# ZOE-M8Q_GPS.net
KiCad netlist of a schematic drawn in EAGLE
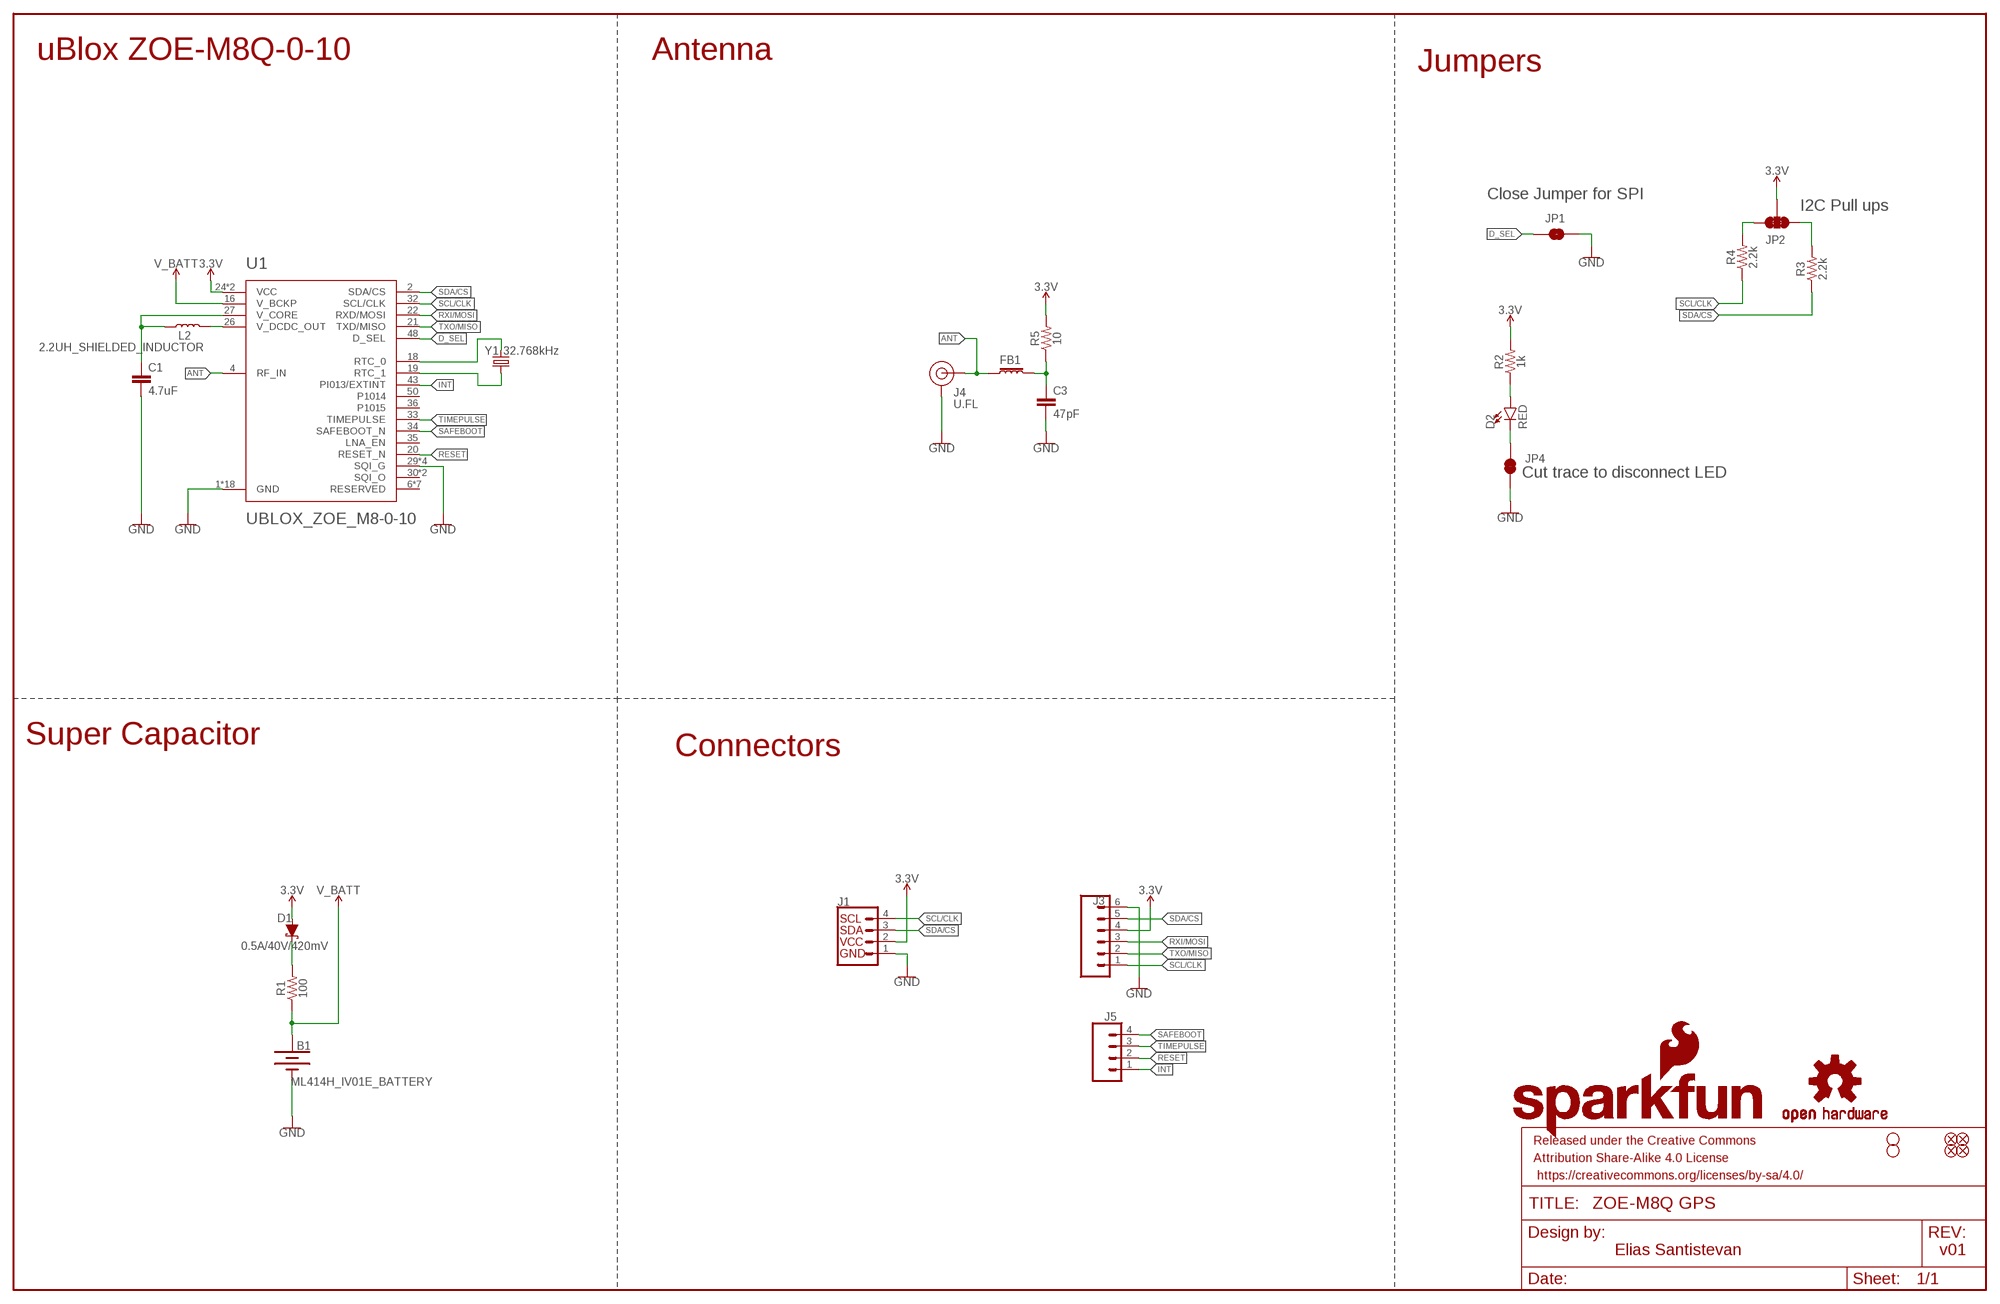
[diagram p0: schematic, sheet 1]

(export (version "E")
  (design (tool "Eeschema 10.0.6"))
  (components
    (comp (ref "B1")
      (value "ML414H_IV01E_BATTERY")
      (footprint "eagle-import:ML414H_IV01E")
      (libsource (lib "eagle-import") (part "ML414H_IV01E_BATTERY"))
    )
    (comp (ref "C1")
      (value "4.7uF")
      (footprint "eagle-import:0603")
      (libsource (lib "eagle-import") (part "4.7UF-0603-6.3V-(10%)"))
    )
    (comp (ref "C3")
      (value "47pF")
      (footprint "eagle-import:0603")
      (libsource (lib "eagle-import") (part "47PF-0603-50V-5%"))
    )
    (comp (ref "D1")
      (value "0.5A/40V/420mV")
      (footprint "eagle-import:SOD-323")
      (libsource (lib "eagle-import") (part "DIODE-SCHOTTKY-PMEG4005EJ"))
    )
    (comp (ref "D2")
      (value "RED")
      (footprint "eagle-import:LED-0603")
      (libsource (lib "eagle-import") (part "LED-RED0603"))
    )
    (comp (ref "FB1")
      (value "FERRITE_BEAD-120_OHM-0402")
      (footprint "eagle-import:0402")
      (fields (field (name "MFG_PART") "BLM15HB121SN1D"))
      (libsource (lib "eagle-import") (part "FERRITE_BEAD-120_OHM-0402"))
    )
    (comp (ref "FD1")
      (value "FIDUCIALUFIDUCIAL")
      (footprint "eagle-import:FIDUCIAL-MICRO")
      (libsource (lib "eagle-import") (part "FIDUCIALUFIDUCIAL"))
    )
    (comp (ref "FD2")
      (value "FIDUCIALUFIDUCIAL")
      (footprint "eagle-import:FIDUCIAL-MICRO")
      (libsource (lib "eagle-import") (part "FIDUCIALUFIDUCIAL"))
    )
    (comp (ref "FD3")
      (value "FIDUCIALUFIDUCIAL")
      (footprint "eagle-import:FIDUCIAL-MICRO")
      (libsource (lib "eagle-import") (part "FIDUCIALUFIDUCIAL"))
    )
    (comp (ref "FD4")
      (value "FIDUCIALUFIDUCIAL")
      (footprint "eagle-import:FIDUCIAL-MICRO")
      (libsource (lib "eagle-import") (part "FIDUCIALUFIDUCIAL"))
    )
    (comp (ref "FRAME1")
      (value "FRAME-LEDGER")
      (footprint "eagle-import:CREATIVE_COMMONS")
      (libsource (lib "eagle-import") (part "FRAME-LEDGER"))
    )
    (comp (ref "H2")
      (value "STAND-OFFTIGHT")
      (footprint "eagle-import:STAND-OFF-TIGHT")
      (libsource (lib "eagle-import") (part "STAND-OFFTIGHT"))
    )
    (comp (ref "H3")
      (value "STAND-OFFTIGHT")
      (footprint "eagle-import:STAND-OFF-TIGHT")
      (libsource (lib "eagle-import") (part "STAND-OFFTIGHT"))
    )
    (comp (ref "J1")
      (value "QWIIC_CONNECTORJS-1MM")
      (footprint "eagle-import:JST04_1MM_RA")
      (libsource (lib "eagle-import") (part "QWIIC_CONNECTORJS-1MM"))
    )
    (comp (ref "J3")
      (value "CONN_06NO_SILK_NO_POP")
      (footprint "eagle-import:1X06_NO_SILK")
      (libsource (lib "eagle-import") (part "CONN_06NO_SILK_NO_POP"))
    )
    (comp (ref "J4")
      (value "U.FL")
      (footprint "eagle-import:U.FL")
      (libsource (lib "eagle-import") (part "U.FL2PIN"))
    )
    (comp (ref "J5")
      (value "CONN_041X04_NO_SILK")
      (footprint "eagle-import:1X04_NO_SILK")
      (libsource (lib "eagle-import") (part "CONN_041X04_NO_SILK"))
    )
    (comp (ref "JP1")
      (value "JUMPER-SMT_2_NO_SILK")
      (footprint "eagle-import:SMT-JUMPER_2_NO_SILK")
      (libsource (lib "eagle-import") (part "JUMPER-SMT_2_NO_SILK"))
    )
    (comp (ref "JP2")
      (value "JUMPER-SMT_3_2-NC_TRACE_SILK")
      (footprint "eagle-import:SMT-JUMPER_3_2-NC_TRACE_SILK")
      (libsource (lib "eagle-import") (part "JUMPER-SMT_3_2-NC_TRACE_SILK"))
    )
    (comp (ref "JP4")
      (value "JUMPER-SMT_2_NC_TRACE_SILK")
      (footprint "eagle-import:SMT-JUMPER_2_NC_TRACE_SILK")
      (libsource (lib "eagle-import") (part "JUMPER-SMT_2_NC_TRACE_SILK"))
    )
    (comp (ref "L2")
      (value "2.2UH_SHIELDED_INDUCTOR")
      (footprint "eagle-import:UNIQUE_0806_NDUC")
      (libsource (lib "eagle-import") (part "2.2UH_SHIELDED_INDUCTOR"))
    )
    (comp (ref "LOGO1")
      (value "SFE_LOGO_NAME_FLAME.1_INCH")
      (footprint "eagle-import:SFE_LOGO_NAME_FLAME_.1")
      (libsource (lib "eagle-import") (part "SFE_LOGO_NAME_FLAME.1_INCH"))
    )
    (comp (ref "LOGO2")
      (value "OSHW-LOGOS")
      (footprint "eagle-import:OSHW-LOGO-S")
      (libsource (lib "eagle-import") (part "OSHW-LOGOS"))
    )
    (comp (ref "LOGO3")
      (value "SFE_LOGO_FLAME.1_INCH")
      (footprint "eagle-import:SFE_LOGO_FLAME_.1")
      (libsource (lib "eagle-import") (part "SFE_LOGO_FLAME.1_INCH"))
    )
    (comp (ref "R1")
      (value "100")
      (footprint "eagle-import:0603")
      (libsource (lib "eagle-import") (part "100OHM-0603-1/10W-1%"))
    )
    (comp (ref "R2")
      (value "1k")
      (footprint "eagle-import:0603")
      (libsource (lib "eagle-import") (part "1KOHM-0603-1/10W-1%"))
    )
    (comp (ref "R3")
      (value "2.2k")
      (footprint "eagle-import:0603")
      (libsource (lib "eagle-import") (part "2.2KOHM-0603-1/10W-1%"))
    )
    (comp (ref "R4")
      (value "2.2k")
      (footprint "eagle-import:0603")
      (libsource (lib "eagle-import") (part "2.2KOHM-0603-1/10W-1%"))
    )
    (comp (ref "R5")
      (value "10")
      (footprint "eagle-import:0603")
      (libsource (lib "eagle-import") (part "10OHM-0603-1/10W-1%"))
    )
    (comp (ref "U1")
      (value "UBLOX_ZOE_M8-0-10")
      (footprint "eagle-import:UBLOX_ZOE_M8-0-10")
      (libsource (lib "eagle-import") (part "UBLOX_ZOE_M8-0-10"))
    )
    (comp (ref "Y1")
      (value "32.768kHz")
      (footprint "eagle-import:CRYSTAL-SMD-3.2X1.5MM")
      (libsource (lib "eagle-import") (part "CRYSTAL-32.768KHZSMD-3.2X1.5"))
    )
  )
  (nets
    (net (code "1") (name "3.3V") (class "Default")
      (node (ref "D1") (pin "A") (pinfunction "A_A") (pintype "passive"))
      (node (ref "J1") (pin "2") (pinfunction "2_2") (pintype "power_in"))
      (node (ref "J3") (pin "4") (pinfunction "4_4") (pintype "passive"))
      (node (ref "JP2") (pin "2") (pinfunction "2_2") (pintype "passive"))
      (node (ref "R2") (pin "2") (pinfunction "2_2") (pintype "passive"))
      (node (ref "R5") (pin "2") (pinfunction "2_2") (pintype "passive"))
      (node (ref "U1") (pin "24") (pinfunction "VCC_24") (pintype "power_in"))
      (node (ref "U1") (pin "25") (pinfunction "VCC_25") (pintype "power_in"))
    )
    (net (code "2") (name "ANT") (class "Default")
      (node (ref "FB1") (pin "1") (pinfunction "1_1") (pintype "passive"))
      (node (ref "J4") (pin "FEED") (pinfunction "SIGNAL_FEED") (pintype "bidirectional"))
      (node (ref "U1") (pin "4") (pinfunction "RF_IN_4") (pintype "bidirectional"))
    )
    (net (code "3") (name "D_SEL") (class "Default")
      (node (ref "JP1") (pin "1") (pinfunction "1_1") (pintype "passive"))
      (node (ref "U1") (pin "48") (pinfunction "D_SEL_48") (pintype "bidirectional"))
    )
    (net (code "4") (name "GND") (class "Default")
      (node (ref "B1") (pin "-") (pinfunction "-_-") (pintype "power_in"))
      (node (ref "C1") (pin "2") (pinfunction "2_2") (pintype "passive"))
      (node (ref "C3") (pin "2") (pinfunction "2_2") (pintype "passive"))
      (node (ref "J1") (pin "1") (pinfunction "1_1") (pintype "power_in"))
      (node (ref "J3") (pin "6") (pinfunction "6_6") (pintype "passive"))
      (node (ref "J4") (pin "1") (pinfunction "GND_1") (pintype "bidirectional"))
      (node (ref "J4") (pin "2") (pinfunction "GND_2") (pintype "bidirectional"))
      (node (ref "JP1") (pin "2") (pinfunction "2_2") (pintype "passive"))
      (node (ref "JP4") (pin "1") (pinfunction "1_1") (pintype "passive"))
      (node (ref "U1") (pin "1") (pinfunction "GND_1") (pintype "power_in"))
      (node (ref "U1") (pin "10") (pinfunction "GND_10") (pintype "power_in"))
      (node (ref "U1") (pin "11") (pinfunction "GND_11") (pintype "power_in"))
      (node (ref "U1") (pin "12") (pinfunction "GND_12") (pintype "power_in"))
      (node (ref "U1") (pin "17") (pinfunction "GND_17") (pintype "power_in"))
      (node (ref "U1") (pin "23") (pinfunction "GND_23") (pintype "power_in"))
      (node (ref "U1") (pin "29") (pinfunction "SQI_G_29") (pintype "bidirectional"))
      (node (ref "U1") (pin "3") (pinfunction "GND_3") (pintype "power_in"))
      (node (ref "U1") (pin "31") (pinfunction "SQI_G_31") (pintype "bidirectional"))
      (node (ref "U1") (pin "37") (pinfunction "GND_37") (pintype "power_in"))
      (node (ref "U1") (pin "38") (pinfunction "GND_38") (pintype "power_in"))
      (node (ref "U1") (pin "39") (pinfunction "GND_39") (pintype "power_in"))
      (node (ref "U1") (pin "40") (pinfunction "GND_40") (pintype "power_in"))
      (node (ref "U1") (pin "41") (pinfunction "GND_41") (pintype "power_in"))
      (node (ref "U1") (pin "44") (pinfunction "GND_44") (pintype "power_in"))
      (node (ref "U1") (pin "46") (pinfunction "SQI_G_46") (pintype "bidirectional"))
      (node (ref "U1") (pin "47") (pinfunction "SQI_G_47") (pintype "bidirectional"))
      (node (ref "U1") (pin "49") (pinfunction "GND_49") (pintype "power_in"))
      (node (ref "U1") (pin "5") (pinfunction "GND_5") (pintype "power_in"))
      (node (ref "U1") (pin "7") (pinfunction "GND_7") (pintype "power_in"))
      (node (ref "U1") (pin "8") (pinfunction "GND_8") (pintype "power_in"))
      (node (ref "U1") (pin "9") (pinfunction "GND_9") (pintype "power_in"))
    )
    (net (code "5") (name "INT") (class "Default")
      (node (ref "J5") (pin "1") (pinfunction "1_1") (pintype "passive"))
      (node (ref "U1") (pin "43") (pinfunction "PI013/EXTINT_43") (pintype "bidirectional"))
    )
    (net (code "6") (name "Net-(C3-Pad1)") (class "Default")
      (node (ref "C3") (pin "1") (pinfunction "1_1") (pintype "passive"))
      (node (ref "FB1") (pin "2") (pinfunction "2_2") (pintype "passive"))
      (node (ref "R5") (pin "1") (pinfunction "1_1") (pintype "passive"))
    )
    (net (code "7") (name "Net-(D1-PadC)") (class "Default")
      (node (ref "D1") (pin "C") (pinfunction "C_C") (pintype "passive"))
      (node (ref "R1") (pin "2") (pinfunction "2_2") (pintype "passive"))
    )
    (net (code "8") (name "Net-(D2-PadA)") (class "Default")
      (node (ref "D2") (pin "A") (pinfunction "A_A") (pintype "passive"))
      (node (ref "R2") (pin "1") (pinfunction "1_1") (pintype "passive"))
    )
    (net (code "9") (name "Net-(D2-PadC)") (class "Default")
      (node (ref "D2") (pin "C") (pinfunction "C_C") (pintype "passive"))
      (node (ref "JP4") (pin "2") (pinfunction "2_2") (pintype "passive"))
    )
    (net (code "10") (name "Net-(JP2-Pad1)") (class "Default")
      (node (ref "JP2") (pin "1") (pinfunction "1_1") (pintype "passive"))
      (node (ref "R3") (pin "2") (pinfunction "2_2") (pintype "passive"))
    )
    (net (code "11") (name "Net-(JP2-Pad3)") (class "Default")
      (node (ref "JP2") (pin "3") (pinfunction "3_3") (pintype "passive"))
      (node (ref "R4") (pin "2") (pinfunction "2_2") (pintype "passive"))
    )
    (net (code "12") (name "Net-(U1-RTC_0)") (class "Default")
      (node (ref "U1") (pin "18") (pinfunction "RTC_0_18") (pintype "bidirectional"))
      (node (ref "Y1") (pin "P$2") (pinfunction "2_P$2") (pintype "passive"))
    )
    (net (code "13") (name "Net-(U1-RTC_1)") (class "Default")
      (node (ref "U1") (pin "19") (pinfunction "RTC_1_19") (pintype "bidirectional"))
      (node (ref "Y1") (pin "P$1") (pinfunction "1_P$1") (pintype "passive"))
    )
    (net (code "14") (name "Net-(U1-V_CORE)") (class "Default")
      (node (ref "C1") (pin "1") (pinfunction "1_1") (pintype "passive"))
      (node (ref "L2") (pin "1") (pinfunction "1_1") (pintype "passive"))
      (node (ref "U1") (pin "27") (pinfunction "V_CORE_27") (pintype "power_in"))
    )
    (net (code "15") (name "Net-(U1-V_DCDC_OUT)") (class "Default")
      (node (ref "L2") (pin "2") (pinfunction "2_2") (pintype "passive"))
      (node (ref "U1") (pin "26") (pinfunction "V_DCDC_OUT_26") (pintype "power_in"))
    )
    (net (code "16") (name "RESET") (class "Default")
      (node (ref "J5") (pin "2") (pinfunction "2_2") (pintype "passive"))
      (node (ref "U1") (pin "20") (pinfunction "RESET_N_20") (pintype "bidirectional"))
    )
    (net (code "17") (name "RXI{slash}MOSI") (class "Default")
      (node (ref "J3") (pin "3") (pinfunction "3_3") (pintype "passive"))
      (node (ref "U1") (pin "22") (pinfunction "RXD/MOSI_22") (pintype "bidirectional"))
    )
    (net (code "18") (name "SAFEBOOT") (class "Default")
      (node (ref "J5") (pin "4") (pinfunction "4_4") (pintype "passive"))
      (node (ref "U1") (pin "34") (pinfunction "SAFEBOOT_N_34") (pintype "bidirectional"))
    )
    (net (code "19") (name "SCL{slash}CLK") (class "Default")
      (node (ref "J1") (pin "4") (pinfunction "4_4") (pintype "passive"))
      (node (ref "J3") (pin "1") (pinfunction "1_1") (pintype "passive"))
      (node (ref "R4") (pin "1") (pinfunction "1_1") (pintype "passive"))
      (node (ref "U1") (pin "32") (pinfunction "SCL/CLK_32") (pintype "bidirectional"))
    )
    (net (code "20") (name "SDA{slash}CS") (class "Default")
      (node (ref "J1") (pin "3") (pinfunction "3_3") (pintype "passive"))
      (node (ref "J3") (pin "5") (pinfunction "5_5") (pintype "passive"))
      (node (ref "R3") (pin "1") (pinfunction "1_1") (pintype "passive"))
      (node (ref "U1") (pin "2") (pinfunction "SDA/CS_2") (pintype "bidirectional"))
    )
    (net (code "21") (name "TIMEPULSE") (class "Default")
      (node (ref "J5") (pin "3") (pinfunction "3_3") (pintype "passive"))
      (node (ref "U1") (pin "33") (pinfunction "TIMEPULSE_33") (pintype "bidirectional"))
    )
    (net (code "22") (name "TXO{slash}MISO") (class "Default")
      (node (ref "J3") (pin "2") (pinfunction "2_2") (pintype "passive"))
      (node (ref "U1") (pin "21") (pinfunction "TXD/MISO_21") (pintype "bidirectional"))
    )
    (net (code "23") (name "V_BATT") (class "Default")
      (node (ref "B1") (pin "+") (pinfunction "+_+") (pintype "power_in"))
      (node (ref "R1") (pin "1") (pinfunction "1_1") (pintype "passive"))
      (node (ref "U1") (pin "16") (pinfunction "V_BCKP_16") (pintype "power_in"))
    )
    (net (code "24") (name "unconnected-(U1-LNA_EN-Pad35)") (class "Default")
      (node (ref "U1") (pin "35") (pinfunction "LNA_EN_35") (pintype "bidirectional"))
    )
    (net (code "25") (name "unconnected-(U1-P1014-Pad50)") (class "Default")
      (node (ref "U1") (pin "50") (pinfunction "P1014_50") (pintype "bidirectional"))
    )
    (net (code "26") (name "unconnected-(U1-P1015-Pad36)") (class "Default")
      (node (ref "U1") (pin "36") (pinfunction "P1015_36") (pintype "bidirectional"))
    )
    (net (code "27") (name "unconnected-(U1-RESERVED-Pad6)") (class "Default")
      (node (ref "U1") (pin "6") (pinfunction "RESERVED_6") (pintype "no_connect"))
    )
    (net (code "28") (name "unconnected-(U1-RESERVED-Pad13)") (class "Default")
      (node (ref "U1") (pin "13") (pinfunction "RESERVED_13") (pintype "no_connect"))
    )
    (net (code "29") (name "unconnected-(U1-RESERVED-Pad14)") (class "Default")
      (node (ref "U1") (pin "14") (pinfunction "RESERVED_14") (pintype "no_connect"))
    )
    (net (code "30") (name "unconnected-(U1-RESERVED-Pad15)") (class "Default")
      (node (ref "U1") (pin "15") (pinfunction "RESERVED_15") (pintype "no_connect"))
    )
    (net (code "31") (name "unconnected-(U1-RESERVED-Pad28)") (class "Default")
      (node (ref "U1") (pin "28") (pinfunction "RESERVED_28") (pintype "no_connect"))
    )
    (net (code "32") (name "unconnected-(U1-RESERVED-Pad42)") (class "Default")
      (node (ref "U1") (pin "42") (pinfunction "RESERVED_42") (pintype "no_connect"))
    )
    (net (code "33") (name "unconnected-(U1-RESERVED-Pad51)") (class "Default")
      (node (ref "U1") (pin "51") (pinfunction "RESERVED_51") (pintype "no_connect"))
    )
    (net (code "34") (name "unconnected-(U1-SQI_O-Pad30)") (class "Default")
      (node (ref "U1") (pin "30") (pinfunction "SQI_O_30") (pintype "no_connect"))
    )
    (net (code "35") (name "unconnected-(U1-SQI_O-Pad45)") (class "Default")
      (node (ref "U1") (pin "45") (pinfunction "SQI_O_45") (pintype "no_connect"))
    )
  )
)
